# Sensors.net
KiCad netlist of a schematic drawn in Altium Designer
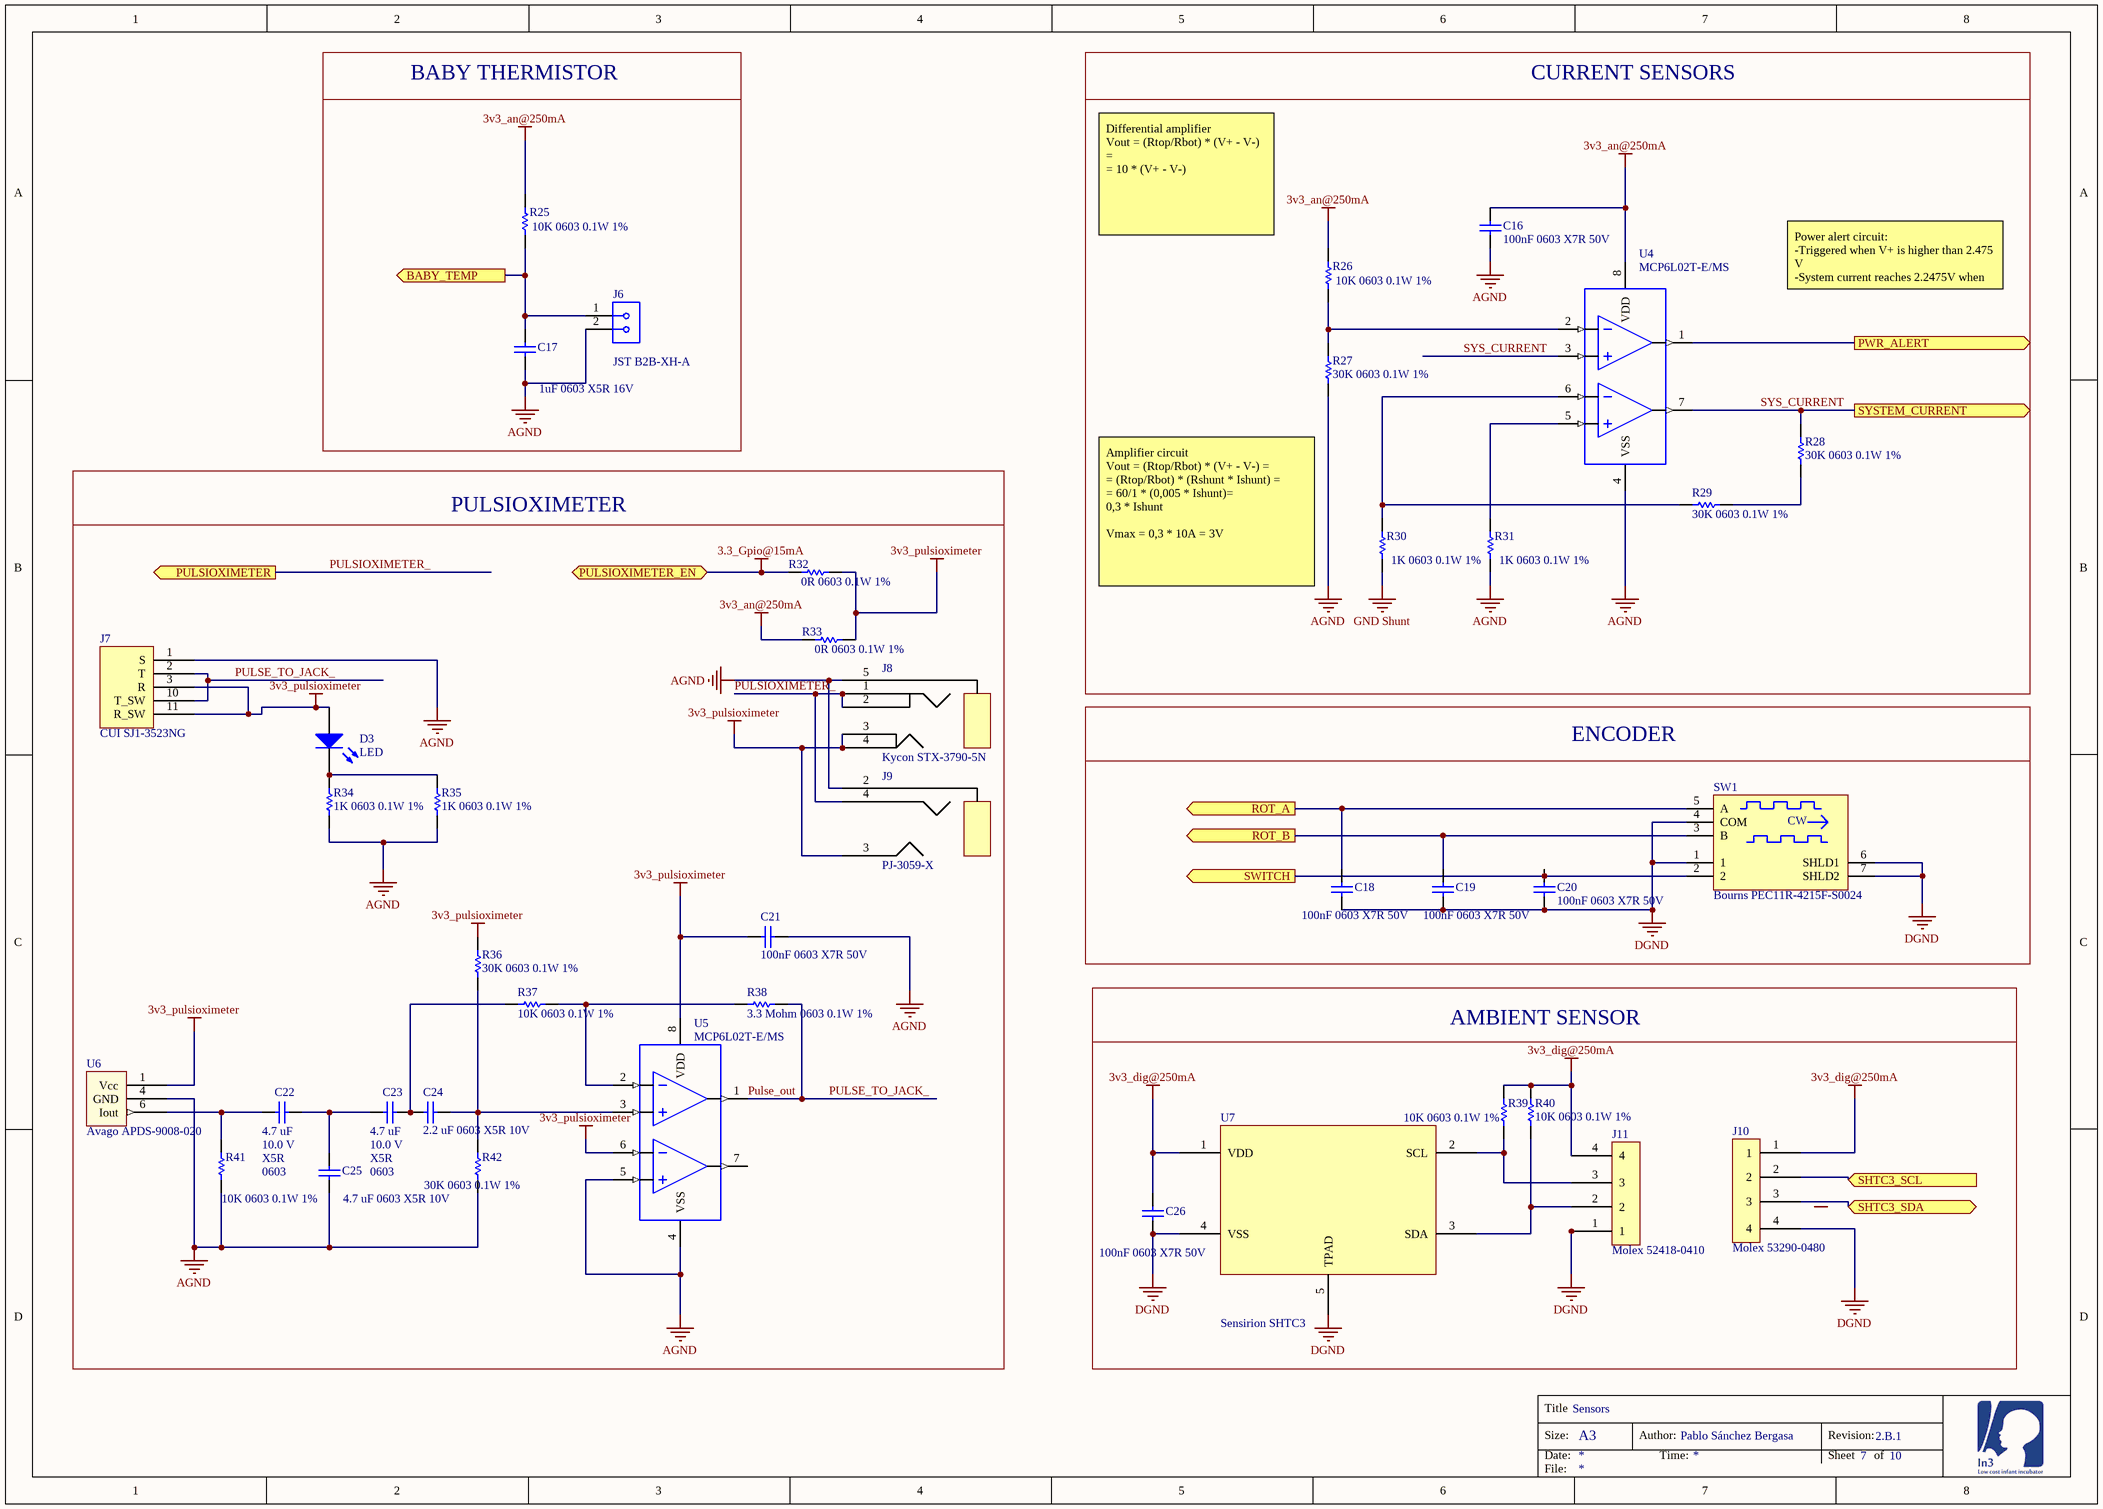
[diagram p0: Sensors.SchDoc]

(export (version "E")
  (design (tool "Eeschema 10.0.6"))
  (components
    (comp (ref "C16")
      (value "100nF 0603 X7R 50V")
      (footprint "CAPC1608X60X35NL10T15")
      (description "100nF 0603 X7R 25V")
      (libsource (lib "CommunityVault") (part "CMP-c41a0d2b65641bdd-3"))
    )
    (comp (ref "C17")
      (value "1uF 0603 X5R 16V")
      (footprint "CAPC1608X60X35NL10T15")
      (fields (field (name "MANUFACTURER PART NUMBER") "GRM185R61C105KE44D"))
      (libsource (lib "CommunityVault") (part "CMP-119984-2"))
    )
    (comp (ref "C18")
      (value "100nF 0603 X7R 50V")
      (footprint "CAPC1608X60X35NL10T15")
      (description "100nF 0603 X7R 25V")
      (libsource (lib "CommunityVault") (part "CMP-c41a0d2b65641bdd-3"))
    )
    (comp (ref "C19")
      (value "100nF 0603 X7R 50V")
      (footprint "CAPC1608X60X35NL10T15")
      (description "100nF 0603 X7R 25V")
      (libsource (lib "CommunityVault") (part "CMP-c41a0d2b65641bdd-3"))
    )
    (comp (ref "C20")
      (value "100nF 0603 X7R 50V")
      (footprint "CAPC1608X60X35NL10T15")
      (description "100nF 0603 X7R 25V")
      (libsource (lib "CommunityVault") (part "CMP-c41a0d2b65641bdd-3"))
    )
    (comp (ref "C21")
      (value "100nF 0603 X7R 50V")
      (footprint "CAPC1608X60X35NL10T15")
      (description "100nF 0603 X7R 25V")
      (libsource (lib "CommunityVault") (part "CMP-c41a0d2b65641bdd-3"))
    )
    (comp (ref "C22")
      (value "4.7 uF 0603 X5R 10V")
      (footprint "PCB-o44e25ijbg7jfnbnmamr-1")
      (description "CL10 Series 4.7 uF 10 V ±10 % Tolerance X5R SMT Multilayer Ceramic Capacitor")
      (fields
        (field (name "CAPACITANCE") "4.7 uF")
        (field (name "MANUFACTURER PART NUMBER") "CL10A475KP8NNNC")
        (field (name "DIELECTRIC CHARACTERISTIC") "X5R")
        (field (name "VOLTAGE RATING (DC)") "10.0 V")
        (field (name "CASE/PACKAGE") "0603")
      )
      (libsource (lib "CommunityVault") (part "CMP-4caf8516eb679368-2"))
    )
    (comp (ref "C23")
      (value "4.7 uF 0603 X5R 10V")
      (footprint "PCB-o44e25ijbg7jfnbnmamr-1")
      (description "CL10 Series 4.7 uF 10 V ±10 % Tolerance X5R SMT Multilayer Ceramic Capacitor")
      (fields
        (field (name "CAPACITANCE") "4.7 uF")
        (field (name "MANUFACTURER PART NUMBER") "CL10A475KP8NNNC")
        (field (name "DIELECTRIC CHARACTERISTIC") "X5R")
        (field (name "VOLTAGE RATING (DC)") "10.0 V")
        (field (name "CASE/PACKAGE") "0603")
      )
      (libsource (lib "CommunityVault") (part "CMP-4caf8516eb679368-2"))
    )
    (comp (ref "C24")
      (value "2.2 uF 0603 X5R 10V")
      (footprint "PCB-ut6qvzar43b06cy077h6-1")
      (description "Capacitor: ceramic; MLCC; 2.2uF; 10V; X5R; ±10%; SMD; 0603; -55÷85°C")
      (fields (field (name "MANUFACTURER PART NUMBER") "CL10A225KP8NNNC"))
      (libsource (lib "CommunityVault") (part "CMP-3568fc1ddfcfeaaf-3"))
    )
    (comp (ref "C25")
      (value "4.7 uF 0603 X5R 10V")
      (footprint "PCB-o44e25ijbg7jfnbnmamr-1")
      (description "CL10 Series 4.7 uF 10 V ±10 % Tolerance X5R SMT Multilayer Ceramic Capacitor")
      (fields (field (name "MANUFACTURER PART NUMBER") "CL10A475KP8NNNC"))
      (libsource (lib "CommunityVault") (part "CMP-4caf8516eb679368-2"))
    )
    (comp (ref "C26")
      (value "100nF 0603 X7R 50V")
      (footprint "CAPC1608X60X35NL10T15")
      (description "100nF 0603 X7R 25V")
      (libsource (lib "CommunityVault") (part "CMP-c41a0d2b65641bdd-3"))
    )
    (comp (ref "D3")
      (value "LED")
      (footprint "Diode")
      (description "Green 2.5 x 2 x 2.8 mm 20° Clear 2700 mcd 3.3 V Subminiature Solid State LED SMT")
      (fields (field (name "MANUFACTURER PART NUMBER") "AM2520ZGC09"))
      (libsource (lib "CommunityVault") (part "CMP-528b9bd0c0208d4c-1"))
    )
    (comp (ref "J6")
      (value "JST B2B-XH-A")
      (footprint "PCB-pp1at3pfx7vls1ur72ey-1")
      (description "Conn Shrouded Header HDR 2 POS 2.5mm Solder ST Thru-Hole Box")
      (fields (field (name "MANUFACTURER PART NUMBER") "B2B-XH-A"))
      (libsource (lib "CommunityVault") (part "CMP-1d67d451da9ec2a0-3"))
    )
    (comp (ref "J7")
      (value "CUI SJ1-3523NG")
      (footprint "PCB-fes4koqfmzto7b0d8kf8-1")
      (description "Conn 3.5MM Stereo Jack RCP 3 POS Solder RA Thru-Hole 3 Terminal 1 Port")
      (fields (field (name "MANUFACTURER PART NUMBER") "SJ1-3523NG"))
      (libsource (lib "CommunityVault") (part "CMP-6d54a45d2240b293-5"))
    )
    (comp (ref "J8")
      (value "Kycon STX-3790-5N")
      (footprint "PCB-4j7k1xhz8vc7zbr3u2za-1")
      (description "Conn Audio RCP 5 POS Solder ST Thru-Hole 5 Terminal 1 Port")
      (fields (field (name "MANUFACTURER PART NUMBER") "STX-3790-5N"))
      (libsource (lib "FavoritesLibrary") (part "SYM-d3711b49a5340cb6-1"))
    )
    (comp (ref "J9")
      (value "PJ-3059-X")
      (footprint "PCB-ylnrsqqp1zh2nrt13053-1")
      (description "3.5mm Plug-in headphone holder")
      (libsource (lib "FavoritesLibrary") (part "SYM-a78f6e8e16b47848-1"))
    )
    (comp (ref "J10")
      (value "Molex 53290-0480")
      (footprint "PCB-az7j7v00du7ll54n3o04-1")
      (description "Molex; SER Number 53290; 2mm Pitch 4Way 1Row Straight PCB Header; Solder Term; 1.5A")
      (fields (field (name "MANUFACTURER PART NUMBER") "53290-0480"))
      (libsource (lib "FavoritesLibrary") (part "SYM-77b5bebc9fe3a872-1"))
    )
    (comp (ref "J11")
      (value "Molex 52418-0410")
      (footprint "PCB-2exqb8kt510pgx9iz0yo-1")
      (description "2.00mm Pitch Board-to-Board Receptacle, Right Angle, Single Row, Friction Lock, 4 Circuits")
      (fields (field (name "MANUFACTURER PART NUMBER") "52418-0410"))
      (libsource (lib "FavoritesLibrary") (part "SYM-efff26f6ba583038-1"))
    )
    (comp (ref "R25")
      (value "10K 0603 0.1W 1%")
      (footprint "RESC1609X55X30ML10T20")
      (fields (field (name "TOLERANCE") "1%"))
      (libsource (lib "CommunityVault") (part "CMP-4716590-9"))
    )
    (comp (ref "R26")
      (value "10K 0603 0.1W 1%")
      (footprint "RESC1609X55X30ML10T20")
      (fields (field (name "TOLERANCE") "1%"))
      (libsource (lib "CommunityVault") (part "CMP-4716590-9"))
    )
    (comp (ref "R27")
      (value "30K 0603 0.1W 1%")
      (footprint "RESC1609X55X30ML10T20")
      (fields (field (name "TOLERANCE") "1%"))
      (libsource (lib "CommunityVault") (part "CMP-3655986-6"))
    )
    (comp (ref "R28")
      (value "30K 0603 0.1W 1%")
      (footprint "RESC1609X55X30ML10T20")
      (fields (field (name "TOLERANCE") "1%"))
      (libsource (lib "CommunityVault") (part "CMP-3655986-6"))
    )
    (comp (ref "R29")
      (value "30K 0603 0.1W 1%")
      (footprint "RESC1609X55X30ML10T20")
      (fields (field (name "TOLERANCE") "1%"))
      (libsource (lib "CommunityVault") (part "CMP-3655986-6"))
    )
    (comp (ref "R30")
      (value "1K 0603 0.1W 1%")
      (footprint "RESC1609X55X30ML10T20")
      (fields (field (name "MANUFACTURER PART NUMBER") "CR0603-FX-1001ELF"))
      (libsource (lib "CommunityVault") (part "CMP-a61f6f36030f79d8-4"))
    )
    (comp (ref "R31")
      (value "1K 0603 0.1W 1%")
      (footprint "RESC1609X55X30ML10T20")
      (fields (field (name "MANUFACTURER PART NUMBER") "CR0603-FX-1001ELF"))
      (libsource (lib "CommunityVault") (part "CMP-a61f6f36030f79d8-4"))
    )
    (comp (ref "R32")
      (value "0R 0603 0.1W 1%")
      (footprint "RESC1609X55X30ML10T20")
      (libsource (lib "CommunityVault") (part "CMP-536b9a7387ce8cac-10"))
    )
    (comp (ref "R33")
      (value "0R 0603 0.1W 1%")
      (footprint "RESC1609X55X30ML10T20")
      (libsource (lib "CommunityVault") (part "CMP-536b9a7387ce8cac-10"))
    )
    (comp (ref "R34")
      (value "1K 0603 0.1W 1%")
      (footprint "RESC1609X55X30ML10T20")
      (fields (field (name "MANUFACTURER PART NUMBER") "CR0603-FX-1001ELF"))
      (libsource (lib "CommunityVault") (part "CMP-a61f6f36030f79d8-4"))
    )
    (comp (ref "R35")
      (value "1K 0603 0.1W 1%")
      (footprint "RESC1609X55X30ML10T20")
      (fields (field (name "MANUFACTURER PART NUMBER") "CR0603-FX-1001ELF"))
      (libsource (lib "CommunityVault") (part "CMP-a61f6f36030f79d8-4"))
    )
    (comp (ref "R36")
      (value "30K 0603 0.1W 1%")
      (footprint "RESC1609X55X30ML10T20")
      (fields (field (name "TOLERANCE") "1%"))
      (libsource (lib "CommunityVault") (part "CMP-3655986-6"))
    )
    (comp (ref "R37")
      (value "10K 0603 0.1W 1%")
      (footprint "RESC1609X55X30ML10T20")
      (fields (field (name "TOLERANCE") "1%"))
      (libsource (lib "CommunityVault") (part "CMP-4716590-9"))
    )
    (comp (ref "R38")
      (value "3.3 Mohm 0603 0.1W 1%")
      (footprint "PCB-mzxdg9kz9211q53vmmjz-1")
      (description "Res Thick Film 1.6 x 0.8 mm 330K Ohm 1% 0.1W(1/10W) 100ppm/ C Molded SMD Paper T/R")
      (fields (field (name "MANUFACTURER PART NUMBER") "RC0603FR-07330KL"))
      (libsource (lib "CommunityVault") (part "CMP-0de3c699ccb2d224-2"))
    )
    (comp (ref "R39")
      (value "10K 0603 0.1W 1%")
      (footprint "RESC1609X55X30ML10T20")
      (fields (field (name "TOLERANCE") "1%"))
      (libsource (lib "CommunityVault") (part "CMP-4716590-9"))
    )
    (comp (ref "R40")
      (value "10K 0603 0.1W 1%")
      (footprint "RESC1609X55X30ML10T20")
      (fields (field (name "TOLERANCE") "1%"))
      (libsource (lib "CommunityVault") (part "CMP-4716590-9"))
    )
    (comp (ref "R41")
      (value "10K 0603 0.1W 1%")
      (footprint "RESC1609X55X30ML10T20")
      (fields (field (name "TOLERANCE") "1%"))
      (libsource (lib "CommunityVault") (part "CMP-4716590-9"))
    )
    (comp (ref "R42")
      (value "30K 0603 0.1W 1%")
      (footprint "RESC1609X55X30ML10T20")
      (fields (field (name "TOLERANCE") "1%"))
      (libsource (lib "CommunityVault") (part "CMP-3655986-6"))
    )
    (comp (ref "SW1")
      (value "Bourns PEC11R-4215F-S0024")
      (footprint "BOUR-PEC11R-4XXXF-SXXXX_V")
      (description "12 mm Incremental Encoder, 24 Detent, -30 to 70 degC, 5-Pin THD, RoHS, Bulk")
      (fields (field (name "MANUFACTURER PART NUMBER") "PEC11R-4215F-S0024"))
      (libsource (lib "FavoritesLibrary") (part "SW-ENCODER-5"))
    )
    (comp (ref "U4")
      (value "MCP6L02T-E/MS")
      (footprint "PCB-e8n0jpjj0ctkgxf737qv-1")
      (description "Microchip MCP6L02T-E/MS, Dual Op Amp, 1MHz Rail-Rail, 1.8 to 6 V, 8-Pin MSOP")
      (libsource (lib "CommunityVault") (part "CMP-1319549-4"))
    )
    (comp (ref "U5")
      (value "MCP6L02T-E/MS")
      (footprint "PCB-e8n0jpjj0ctkgxf737qv-1")
      (description "Microchip MCP6L02T-E/MS, Dual Op Amp, 1MHz Rail-Rail, 1.8 to 6 V, 8-Pin MSOP")
      (libsource (lib "CommunityVault") (part "CMP-1319549-4"))
    )
    (comp (ref "U6")
      (value "Avago APDS-9008-020")
      (footprint "PCB-5zuy5omviewwv0vuvsb9-1")
      (description "Ambient Light Sensor Photodetector 6-Pin SMD T/R")
      (fields (field (name "MANUFACTURER PART NUMBER") "APDS-9008-020"))
      (libsource (lib "CommunityVault") (part "SYM-1600df74f371c9c7-1"))
    )
    (comp (ref "U7")
      (value "Sensirion SHTC3")
      (footprint "DFN4 2x2 + EP")
      (description "Humidity & Temperature Sensor ±2% RH ±0, 2°C I2C DFN4")
      (libsource (lib "CommunityVault") (part "SHTC3"))
    )
  )
  (nets
    (net (code "1") (name "/BABY_TEMP") (class "Default")
      (node (ref "C17") (pin "1") (pinfunction "1_1") (pintype "passive"))
      (node (ref "J6") (pin "1") (pinfunction "1_1") (pintype "passive"))
      (node (ref "R25") (pin "1") (pinfunction "1_1") (pintype "passive"))
    )
    (net (code "2") (name "/PULSE_TO_JACK_") (class "Default")
      (node (ref "J7") (pin "10") (pinfunction "T_SW_10") (pintype "passive"))
      (node (ref "J7") (pin "2") (pinfunction "T_2") (pintype "passive"))
      (node (ref "R38") (pin "2") (pinfunction "2_2") (pintype "passive"))
      (node (ref "U5") (pin "1") (pinfunction "VOUTA_1") (pintype "output"))
    )
    (net (code "3") (name "/PULSIOXIMETER_") (class "Default")
      (node (ref "J8") (pin "1") (pinfunction "RIGHT_1") (pintype "passive"))
      (node (ref "J8") (pin "2") (pinfunction "RIGHT_2") (pintype "passive"))
      (node (ref "J9") (pin "4") (pinfunction "RIGHT_4") (pintype "passive"))
    )
    (net (code "4") (name "/PWR_ALERT") (class "Default")
      (node (ref "U4") (pin "1") (pinfunction "VOUTA_1") (pintype "output"))
    )
    (net (code "5") (name "/ROT_A") (class "Default")
      (node (ref "C18") (pin "2") (pinfunction "2_2") (pintype "passive"))
      (node (ref "SW1") (pin "5") (pinfunction "A_5") (pintype "passive"))
    )
    (net (code "6") (name "/ROT_B") (class "Default")
      (node (ref "C19") (pin "2") (pinfunction "2_2") (pintype "passive"))
      (node (ref "SW1") (pin "3") (pinfunction "B_3") (pintype "passive"))
    )
    (net (code "7") (name "/SHTC3_SCL") (class "Default")
      (node (ref "J10") (pin "2") (pinfunction "2_2") (pintype "passive"))
    )
    (net (code "8") (name "/SHTC3_SDA") (class "Default")
      (node (ref "J10") (pin "3") (pinfunction "3_3") (pintype "passive"))
    )
    (net (code "9") (name "/SWITCH") (class "Default")
      (node (ref "C20") (pin "2") (pinfunction "2_2") (pintype "passive"))
      (node (ref "SW1") (pin "2") (pinfunction "2_2") (pintype "passive"))
    )
    (net (code "10") (name "/SYS_CURRENT") (class "Default")
      (node (ref "R28") (pin "1") (pinfunction "1_1") (pintype "passive"))
      (node (ref "U4") (pin "3") (pinfunction "VINA+_3") (pintype "input"))
      (node (ref "U4") (pin "7") (pinfunction "OUT_B_7") (pintype "output"))
    )
    (net (code "11") (name "3.3_Gpio@15mA") (class "Default")
      (node (ref "R32") (pin "1") (pinfunction "1_1") (pintype "passive"))
    )
    (net (code "12") (name "3v3_an@250mA") (class "Default")
      (node (ref "C16") (pin "2") (pinfunction "2_2") (pintype "passive"))
      (node (ref "R25") (pin "2") (pinfunction "2_2") (pintype "passive"))
      (node (ref "R26") (pin "2") (pinfunction "2_2") (pintype "passive"))
      (node (ref "R33") (pin "1") (pinfunction "1_1") (pintype "passive"))
      (node (ref "U4") (pin "8") (pinfunction "VDD_8") (pintype "power_in"))
    )
    (net (code "13") (name "3v3_dig@250mA") (class "Default")
      (node (ref "C26") (pin "1") (pinfunction "1_1") (pintype "passive"))
      (node (ref "J10") (pin "1") (pinfunction "1_1") (pintype "passive"))
      (node (ref "J11") (pin "4") (pinfunction "4_4") (pintype "passive"))
      (node (ref "R39") (pin "1") (pinfunction "1_1") (pintype "passive"))
      (node (ref "R40") (pin "1") (pinfunction "1_1") (pintype "passive"))
      (node (ref "U7") (pin "1") (pinfunction "VDD_1") (pintype "passive"))
    )
    (net (code "14") (name "3v3_pulsioximeter") (class "Default")
      (node (ref "C21") (pin "2") (pinfunction "2_2") (pintype "passive"))
      (node (ref "D3") (pin "1") (pinfunction "A_1") (pintype "passive"))
      (node (ref "J7") (pin "11") (pinfunction "R_SW_11") (pintype "passive"))
      (node (ref "J7") (pin "3") (pinfunction "R_3") (pintype "passive"))
      (node (ref "J8") (pin "3") (pinfunction "RIGHT_3") (pintype "passive"))
      (node (ref "J8") (pin "4") (pinfunction "LEFT_4") (pintype "passive"))
      (node (ref "J9") (pin "3") (pinfunction "LEFT_3") (pintype "passive"))
      (node (ref "R32") (pin "2") (pinfunction "2_2") (pintype "passive"))
      (node (ref "R33") (pin "2") (pinfunction "2_2") (pintype "passive"))
      (node (ref "R36") (pin "1") (pinfunction "1_1") (pintype "passive"))
      (node (ref "U5") (pin "6") (pinfunction "VINB-_6") (pintype "input"))
      (node (ref "U5") (pin "8") (pinfunction "VDD_8") (pintype "power_in"))
      (node (ref "U6") (pin "1") (pinfunction "Vcc_1") (pintype "power_in"))
    )
    (net (code "15") (name "AGND") (class "Default")
      (node (ref "C16") (pin "1") (pinfunction "1_1") (pintype "passive"))
      (node (ref "C17") (pin "2") (pinfunction "2_2") (pintype "passive"))
      (node (ref "C21") (pin "1") (pinfunction "1_1") (pintype "passive"))
      (node (ref "C25") (pin "2") (pinfunction "2_2") (pintype "passive"))
      (node (ref "J6") (pin "2") (pinfunction "2_2") (pintype "passive"))
      (node (ref "J7") (pin "1") (pinfunction "S_1") (pintype "passive"))
      (node (ref "J8") (pin "5") (pinfunction "GND_5") (pintype "passive"))
      (node (ref "J9") (pin "2") (pinfunction "GND_2") (pintype "passive"))
      (node (ref "R27") (pin "2") (pinfunction "2_2") (pintype "passive"))
      (node (ref "R31") (pin "1") (pinfunction "1_1") (pintype "passive"))
      (node (ref "R34") (pin "1") (pinfunction "1_1") (pintype "passive"))
      (node (ref "R35") (pin "1") (pinfunction "1_1") (pintype "passive"))
      (node (ref "R41") (pin "1") (pinfunction "1_1") (pintype "passive"))
      (node (ref "R42") (pin "2") (pinfunction "2_2") (pintype "passive"))
      (node (ref "U4") (pin "4") (pinfunction "VSS_4") (pintype "power_in"))
      (node (ref "U5") (pin "4") (pinfunction "VSS_4") (pintype "power_in"))
      (node (ref "U5") (pin "5") (pinfunction "VINB+_5") (pintype "input"))
      (node (ref "U6") (pin "4") (pinfunction "GND_4") (pintype "power_in"))
    )
    (net (code "16") (name "DGND") (class "Default")
      (node (ref "C18") (pin "1") (pinfunction "1_1") (pintype "passive"))
      (node (ref "C19") (pin "1") (pinfunction "1_1") (pintype "passive"))
      (node (ref "C20") (pin "1") (pinfunction "1_1") (pintype "passive"))
      (node (ref "C26") (pin "2") (pinfunction "2_2") (pintype "passive"))
      (node (ref "J10") (pin "4") (pinfunction "4_4") (pintype "passive"))
      (node (ref "J11") (pin "1") (pinfunction "1_1") (pintype "passive"))
      (node (ref "SW1") (pin "1") (pinfunction "1_1") (pintype "passive"))
      (node (ref "SW1") (pin "4") (pinfunction "COM_4") (pintype "passive"))
      (node (ref "SW1") (pin "6") (pinfunction "SHLD1_6") (pintype "passive"))
      (node (ref "SW1") (pin "7") (pinfunction "SHLD2_7") (pintype "passive"))
      (node (ref "U7") (pin "4") (pinfunction "VSS_4") (pintype "passive"))
      (node (ref "U7") (pin "5") (pinfunction "TPAD_5") (pintype "passive"))
    )
    (net (code "17") (name "GND Shunt") (class "Default")
      (node (ref "R30") (pin "1") (pinfunction "1_1") (pintype "passive"))
    )
    (net (code "18") (name "Net-(C22-Pad1)") (class "Default")
      (node (ref "C22") (pin "1") (pinfunction "1_1") (pintype "passive"))
      (node (ref "C23") (pin "2") (pinfunction "2_2") (pintype "passive"))
      (node (ref "C25") (pin "1") (pinfunction "1_1") (pintype "passive"))
    )
    (net (code "19") (name "Net-(C23-Pad1)") (class "Default")
      (node (ref "C23") (pin "1") (pinfunction "1_1") (pintype "passive"))
      (node (ref "C24") (pin "2") (pinfunction "2_2") (pintype "passive"))
      (node (ref "R37") (pin "2") (pinfunction "2_2") (pintype "passive"))
    )
    (net (code "20") (name "Net-(D3-K)") (class "Default")
      (node (ref "D3") (pin "2") (pinfunction "K_2") (pintype "passive"))
      (node (ref "R34") (pin "2") (pinfunction "2_2") (pintype "passive"))
      (node (ref "R35") (pin "2") (pinfunction "2_2") (pintype "passive"))
    )
    (net (code "21") (name "Net-(R28-Pad2)") (class "Default")
      (node (ref "R28") (pin "2") (pinfunction "2_2") (pintype "passive"))
      (node (ref "R29") (pin "2") (pinfunction "2_2") (pintype "passive"))
    )
    (net (code "22") (name "Net-(U4-VINA-)") (class "Default")
      (node (ref "R26") (pin "1") (pinfunction "1_1") (pintype "passive"))
      (node (ref "R27") (pin "1") (pinfunction "1_1") (pintype "passive"))
      (node (ref "U4") (pin "2") (pinfunction "VINA-_2") (pintype "input"))
    )
    (net (code "23") (name "Net-(U4-VINB+)") (class "Default")
      (node (ref "R31") (pin "2") (pinfunction "2_2") (pintype "passive"))
      (node (ref "U4") (pin "5") (pinfunction "VINB+_5") (pintype "input"))
    )
    (net (code "24") (name "Net-(U4-VINB-)") (class "Default")
      (node (ref "R29") (pin "1") (pinfunction "1_1") (pintype "passive"))
      (node (ref "R30") (pin "2") (pinfunction "2_2") (pintype "passive"))
      (node (ref "U4") (pin "6") (pinfunction "VINB-_6") (pintype "input"))
    )
    (net (code "25") (name "Net-(U5-VINA+)") (class "Default")
      (node (ref "C24") (pin "1") (pinfunction "1_1") (pintype "passive"))
      (node (ref "R36") (pin "2") (pinfunction "2_2") (pintype "passive"))
      (node (ref "R42") (pin "1") (pinfunction "1_1") (pintype "passive"))
      (node (ref "U5") (pin "3") (pinfunction "VINA+_3") (pintype "input"))
    )
    (net (code "26") (name "Net-(U5-VINA-)") (class "Default")
      (node (ref "R37") (pin "1") (pinfunction "1_1") (pintype "passive"))
      (node (ref "R38") (pin "1") (pinfunction "1_1") (pintype "passive"))
      (node (ref "U5") (pin "2") (pinfunction "VINA-_2") (pintype "input"))
    )
    (net (code "27") (name "Net-(U6-Iout)") (class "Default")
      (node (ref "C22") (pin "2") (pinfunction "2_2") (pintype "passive"))
      (node (ref "R41") (pin "2") (pinfunction "2_2") (pintype "passive"))
      (node (ref "U6") (pin "6") (pinfunction "Iout_6") (pintype "output"))
    )
    (net (code "28") (name "Net-(U7-SCL)") (class "Default")
      (node (ref "J11") (pin "3") (pinfunction "3_3") (pintype "passive"))
      (node (ref "R39") (pin "2") (pinfunction "2_2") (pintype "passive"))
      (node (ref "U7") (pin "2") (pinfunction "SCL_2") (pintype "passive"))
    )
    (net (code "29") (name "Net-(U7-SDA)") (class "Default")
      (node (ref "J11") (pin "2") (pinfunction "2_2") (pintype "passive"))
      (node (ref "R40") (pin "2") (pinfunction "2_2") (pintype "passive"))
      (node (ref "U7") (pin "3") (pinfunction "SDA_3") (pintype "passive"))
    )
    (net (code "30") (name "unconnected-(U5-OUT_B-Pad7)") (class "Default")
      (node (ref "U5") (pin "7") (pinfunction "OUT_B_7") (pintype "output"))
    )
  )
)
